# SlaveProtect.net
KiCad netlist of a schematic drawn in EAGLE
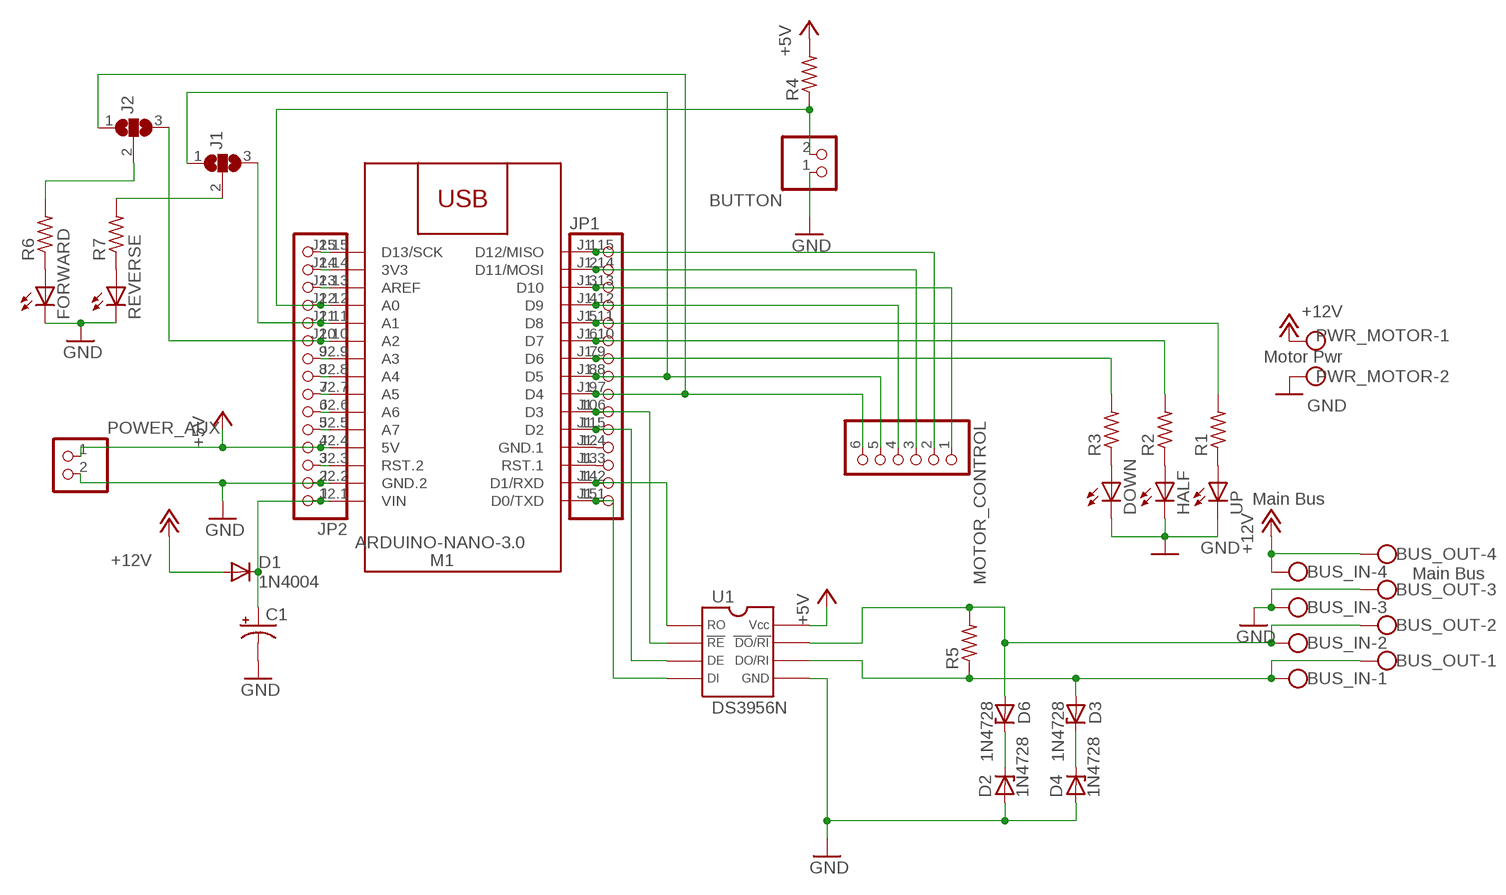
[diagram p0: schematic, sheet 1]

(export (version "E")
  (design (tool "Eeschema 10.0.6"))
  (components
    (comp (ref "BUS_IN")
      (value "Main Bus")
      (footprint "eagle-import:W237-4")
      (libsource (lib "eagle-import") (part "W237-4"))
    )
    (comp (ref "BUS_OUT")
      (value "Main Bus")
      (footprint "eagle-import:W237-4")
      (libsource (lib "eagle-import") (part "W237-4"))
    )
    (comp (ref "BUTTON")
      (value "PINHD-1X2")
      (footprint "eagle-import:1X02")
      (libsource (lib "eagle-import") (part "PINHD-1X2"))
    )
    (comp (ref "C1")
      (value "CPOL-USE3.5-10")
      (footprint "eagle-import:E3,5-10")
      (libsource (lib "eagle-import") (part "CPOL-USE3.5-10"))
    )
    (comp (ref "D1")
      (value "1N4004")
      (footprint "eagle-import:DO41-10")
      (libsource (lib "eagle-import") (part "1N4004"))
    )
    (comp (ref "D2")
      (value "1N4728")
      (footprint "eagle-import:DO41Z10")
      (libsource (lib "eagle-import") (part "1N4728"))
    )
    (comp (ref "D3")
      (value "1N4728")
      (footprint "eagle-import:DO41Z10")
      (libsource (lib "eagle-import") (part "1N4728"))
    )
    (comp (ref "D4")
      (value "1N4728")
      (footprint "eagle-import:DO41Z10")
      (libsource (lib "eagle-import") (part "1N4728"))
    )
    (comp (ref "D6")
      (value "1N4728")
      (footprint "eagle-import:DO41Z10")
      (libsource (lib "eagle-import") (part "1N4728"))
    )
    (comp (ref "DOWN")
      (value "LED5MM")
      (footprint "eagle-import:LED5MM")
      (libsource (lib "eagle-import") (part "LED5MM"))
    )
    (comp (ref "FORWARD")
      (value "LED5MM")
      (footprint "eagle-import:LED5MM")
      (libsource (lib "eagle-import") (part "LED5MM"))
    )
    (comp (ref "HALF")
      (value "LED5MM")
      (footprint "eagle-import:LED5MM")
      (libsource (lib "eagle-import") (part "LED5MM"))
    )
    (comp (ref "J1")
      (value "SJ2W")
      (footprint "eagle-import:SJ_2")
      (libsource (lib "eagle-import") (part "SJ2W"))
    )
    (comp (ref "J2")
      (value "SJ2W")
      (footprint "eagle-import:SJ_2")
      (libsource (lib "eagle-import") (part "SJ2W"))
    )
    (comp (ref "JP1")
      (value "PINHD-1X15-CB")
      (footprint "eagle-import:1X15-CB")
      (libsource (lib "eagle-import") (part "PINHD-1X15-CB"))
    )
    (comp (ref "JP2")
      (value "PINHD-1X15-CB")
      (footprint "eagle-import:1X15-CB")
      (libsource (lib "eagle-import") (part "PINHD-1X15-CB"))
    )
    (comp (ref "M1")
      (value "ARDUINO-NANO-3.0")
      (footprint "eagle-import:ARDUINO-NANO-3.0")
      (libsource (lib "eagle-import") (part "ARDUINO-NANO-3.0"))
    )
    (comp (ref "MOTOR_CONTROL")
      (value "PINHD-1X6")
      (footprint "eagle-import:1X06")
      (libsource (lib "eagle-import") (part "PINHD-1X6"))
    )
    (comp (ref "POWER_AUX")
      (value "PINHD-1X2")
      (footprint "eagle-import:1X02")
      (libsource (lib "eagle-import") (part "PINHD-1X2"))
    )
    (comp (ref "PWR_MOTOR")
      (value "Motor Pwr")
      (footprint "eagle-import:W237-102")
      (fields (field (name "MPN") "237-102"))
      (libsource (lib "eagle-import") (part "W237-102"))
    )
    (comp (ref "R1")
      (value "FLIPFLOP-RES")
      (footprint "eagle-import:0805-THM")
      (libsource (lib "eagle-import") (part "FLIPFLOP-RES"))
    )
    (comp (ref "R2")
      (value "FLIPFLOP-RES")
      (footprint "eagle-import:0805-THM")
      (libsource (lib "eagle-import") (part "FLIPFLOP-RES"))
    )
    (comp (ref "R3")
      (value "FLIPFLOP-RES")
      (footprint "eagle-import:0805-THM")
      (libsource (lib "eagle-import") (part "FLIPFLOP-RES"))
    )
    (comp (ref "R4")
      (value "FLIPFLOP-RES")
      (footprint "eagle-import:0805-THM")
      (libsource (lib "eagle-import") (part "FLIPFLOP-RES"))
    )
    (comp (ref "R5")
      (value "FLIPFLOP-RES")
      (footprint "eagle-import:0805-THM")
      (libsource (lib "eagle-import") (part "FLIPFLOP-RES"))
    )
    (comp (ref "R6")
      (value "FLIPFLOP-RES")
      (footprint "eagle-import:0805-THM")
      (libsource (lib "eagle-import") (part "FLIPFLOP-RES"))
    )
    (comp (ref "R7")
      (value "FLIPFLOP-RES")
      (footprint "eagle-import:0805-THM")
      (libsource (lib "eagle-import") (part "FLIPFLOP-RES"))
    )
    (comp (ref "REVERSE")
      (value "LED5MM")
      (footprint "eagle-import:LED5MM")
      (libsource (lib "eagle-import") (part "LED5MM"))
    )
    (comp (ref "U1")
      (value "DS3956N")
      (footprint "eagle-import:DIL08")
      (libsource (lib "eagle-import") (part "DS3956N"))
    )
    (comp (ref "UP")
      (value "LED5MM")
      (footprint "eagle-import:LED5MM")
      (libsource (lib "eagle-import") (part "LED5MM"))
    )
  )
  (nets
    (net (code "1") (name "+5V") (class "Default")
      (node (ref "JP2") (pin "4") (pinfunction "4_4") (pintype "passive"))
      (node (ref "M1") (pin "J2.4") (pinfunction "5V_J2.4") (pintype "power_in"))
      (node (ref "POWER_AUX") (pin "1") (pinfunction "1_1") (pintype "passive"))
      (node (ref "R4") (pin "2") (pinfunction "2_2") (pintype "passive"))
      (node (ref "U1") (pin "8") (pinfunction "VCC_8") (pintype "bidirectional"))
    )
    (net (code "2") (name "+12V") (class "Default")
      (node (ref "BUS_IN") (pin "4") (pinfunction "KL_4") (pintype "passive"))
      (node (ref "BUS_OUT") (pin "4") (pinfunction "KL_4") (pintype "passive"))
      (node (ref "D1") (pin "A") (pinfunction "A_A") (pintype "passive"))
      (node (ref "PWR_MOTOR") (pin "1") (pinfunction "KL_1") (pintype "passive"))
    )
    (net (code "3") (name "GND") (class "Default")
      (node (ref "BUS_IN") (pin "3") (pinfunction "KL_3") (pintype "passive"))
      (node (ref "BUS_OUT") (pin "3") (pinfunction "KL_3") (pintype "passive"))
      (node (ref "BUTTON") (pin "1") (pinfunction "1_1") (pintype "passive"))
      (node (ref "C1") (pin "-") (pinfunction "-_-") (pintype "passive"))
      (node (ref "D2") (pin "A") (pinfunction "A_A") (pintype "passive"))
      (node (ref "D4") (pin "A") (pinfunction "A_A") (pintype "passive"))
      (node (ref "DOWN") (pin "K") (pinfunction "C_K") (pintype "passive"))
      (node (ref "FORWARD") (pin "K") (pinfunction "C_K") (pintype "passive"))
      (node (ref "HALF") (pin "K") (pinfunction "C_K") (pintype "passive"))
      (node (ref "JP2") (pin "2") (pinfunction "2_2") (pintype "passive"))
      (node (ref "M1") (pin "J2.2") (pinfunction "GND.2_J2.2") (pintype "power_in"))
      (node (ref "POWER_AUX") (pin "2") (pinfunction "2_2") (pintype "passive"))
      (node (ref "PWR_MOTOR") (pin "2") (pinfunction "KL_2") (pintype "passive"))
      (node (ref "REVERSE") (pin "K") (pinfunction "C_K") (pintype "passive"))
      (node (ref "U1") (pin "5") (pinfunction "GND_5") (pintype "bidirectional"))
      (node (ref "UP") (pin "K") (pinfunction "C_K") (pintype "passive"))
    )
    (net (code "4") (name "Net-(BUS_INA-KL)") (class "Default")
      (node (ref "BUS_IN") (pin "1") (pinfunction "KL_1") (pintype "passive"))
      (node (ref "BUS_OUT") (pin "1") (pinfunction "KL_1") (pintype "passive"))
      (node (ref "D3") (pin "A") (pinfunction "A_A") (pintype "passive"))
      (node (ref "R5") (pin "1") (pinfunction "1_1") (pintype "passive"))
      (node (ref "U1") (pin "6") (pinfunction "DO/RI_6") (pintype "bidirectional"))
    )
    (net (code "5") (name "Net-(BUS_INB-KL)") (class "Default")
      (node (ref "BUS_IN") (pin "2") (pinfunction "KL_2") (pintype "passive"))
      (node (ref "BUS_OUT") (pin "2") (pinfunction "KL_2") (pintype "passive"))
      (node (ref "D6") (pin "A") (pinfunction "A_A") (pintype "passive"))
      (node (ref "R5") (pin "2") (pinfunction "2_2") (pintype "passive"))
      (node (ref "U1") (pin "7") (pinfunction "_DO/RI__7") (pintype "bidirectional"))
    )
    (net (code "6") (name "Net-(D2-PadC)") (class "Default")
      (node (ref "D2") (pin "C") (pinfunction "C_C") (pintype "passive"))
      (node (ref "D6") (pin "C") (pinfunction "C_C") (pintype "passive"))
    )
    (net (code "7") (name "Net-(D3-PadC)") (class "Default")
      (node (ref "D3") (pin "C") (pinfunction "C_C") (pintype "passive"))
      (node (ref "D4") (pin "C") (pinfunction "C_C") (pintype "passive"))
    )
    (net (code "8") (name "Net-(DOWN-PadA)") (class "Default")
      (node (ref "DOWN") (pin "A") (pinfunction "A_A") (pintype "passive"))
      (node (ref "R3") (pin "1") (pinfunction "1_1") (pintype "passive"))
    )
    (net (code "9") (name "Net-(FORWARD-PadA)") (class "Default")
      (node (ref "FORWARD") (pin "A") (pinfunction "A_A") (pintype "passive"))
      (node (ref "R6") (pin "1") (pinfunction "1_1") (pintype "passive"))
    )
    (net (code "10") (name "Net-(HALF-PadA)") (class "Default")
      (node (ref "HALF") (pin "A") (pinfunction "A_A") (pintype "passive"))
      (node (ref "R2") (pin "1") (pinfunction "1_1") (pintype "passive"))
    )
    (net (code "11") (name "Net-(J1-Pad2)") (class "Default")
      (node (ref "J1") (pin "2") (pinfunction "2_2") (pintype "passive"))
      (node (ref "R7") (pin "2") (pinfunction "2_2") (pintype "passive"))
    )
    (net (code "12") (name "Net-(J2-Pad2)") (class "Default")
      (node (ref "J2") (pin "2") (pinfunction "2_2") (pintype "passive"))
      (node (ref "R6") (pin "2") (pinfunction "2_2") (pintype "passive"))
    )
    (net (code "13") (name "Net-(M1-3V3)") (class "Default")
      (node (ref "JP2") (pin "14") (pinfunction "14_14") (pintype "passive"))
      (node (ref "M1") (pin "J2.14") (pinfunction "3V3_J2.14") (pintype "power_in"))
    )
    (net (code "14") (name "Net-(M1-A0)") (class "Default")
      (node (ref "BUTTON") (pin "2") (pinfunction "2_2") (pintype "passive"))
      (node (ref "JP2") (pin "12") (pinfunction "12_12") (pintype "passive"))
      (node (ref "M1") (pin "J2.12") (pinfunction "A0_J2.12") (pintype "bidirectional"))
      (node (ref "R4") (pin "1") (pinfunction "1_1") (pintype "passive"))
    )
    (net (code "15") (name "Net-(M1-A1)") (class "Default")
      (node (ref "J1") (pin "3") (pinfunction "3_3") (pintype "passive"))
      (node (ref "JP2") (pin "11") (pinfunction "11_11") (pintype "passive"))
      (node (ref "M1") (pin "J2.11") (pinfunction "A1_J2.11") (pintype "bidirectional"))
    )
    (net (code "16") (name "Net-(M1-A2)") (class "Default")
      (node (ref "J2") (pin "3") (pinfunction "3_3") (pintype "passive"))
      (node (ref "JP2") (pin "10") (pinfunction "10_10") (pintype "passive"))
      (node (ref "M1") (pin "J2.10") (pinfunction "A2_J2.10") (pintype "bidirectional"))
    )
    (net (code "17") (name "Net-(M1-A3)") (class "Default")
      (node (ref "JP2") (pin "9") (pinfunction "9_9") (pintype "passive"))
      (node (ref "M1") (pin "J2.9") (pinfunction "A3_J2.9") (pintype "bidirectional"))
    )
    (net (code "18") (name "Net-(M1-A4)") (class "Default")
      (node (ref "JP2") (pin "8") (pinfunction "8_8") (pintype "passive"))
      (node (ref "M1") (pin "J2.8") (pinfunction "A4_J2.8") (pintype "bidirectional"))
    )
    (net (code "19") (name "Net-(M1-A5)") (class "Default")
      (node (ref "JP2") (pin "7") (pinfunction "7_7") (pintype "passive"))
      (node (ref "M1") (pin "J2.7") (pinfunction "A5_J2.7") (pintype "bidirectional"))
    )
    (net (code "20") (name "Net-(M1-A6)") (class "Default")
      (node (ref "JP2") (pin "6") (pinfunction "6_6") (pintype "passive"))
      (node (ref "M1") (pin "J2.6") (pinfunction "A6_J2.6") (pintype "bidirectional"))
    )
    (net (code "21") (name "Net-(M1-A7)") (class "Default")
      (node (ref "JP2") (pin "5") (pinfunction "5_5") (pintype "passive"))
      (node (ref "M1") (pin "J2.5") (pinfunction "A7_J2.5") (pintype "bidirectional"))
    )
    (net (code "22") (name "Net-(M1-AREF)") (class "Default")
      (node (ref "JP2") (pin "13") (pinfunction "13_13") (pintype "passive"))
      (node (ref "M1") (pin "J2.13") (pinfunction "AREF_J2.13") (pintype "bidirectional"))
    )
    (net (code "23") (name "Net-(M1-D0{slash}TXD)") (class "Default")
      (node (ref "JP1") (pin "15") (pinfunction "15_15") (pintype "passive"))
      (node (ref "M1") (pin "J1.1") (pinfunction "D0/TXD_J1.1") (pintype "bidirectional"))
      (node (ref "U1") (pin "4") (pinfunction "DI_4") (pintype "bidirectional"))
    )
    (net (code "24") (name "Net-(M1-D1{slash}RXD)") (class "Default")
      (node (ref "JP1") (pin "14") (pinfunction "14_14") (pintype "passive"))
      (node (ref "M1") (pin "J1.2") (pinfunction "D1/RXD_J1.2") (pintype "bidirectional"))
      (node (ref "U1") (pin "1") (pinfunction "RO_1") (pintype "bidirectional"))
    )
    (net (code "25") (name "Net-(M1-D2)") (class "Default")
      (node (ref "JP1") (pin "11") (pinfunction "11_11") (pintype "passive"))
      (node (ref "M1") (pin "J1.5") (pinfunction "D2_J1.5") (pintype "bidirectional"))
      (node (ref "U1") (pin "3") (pinfunction "DE_3") (pintype "bidirectional"))
    )
    (net (code "26") (name "Net-(M1-D3)") (class "Default")
      (node (ref "JP1") (pin "10") (pinfunction "10_10") (pintype "passive"))
      (node (ref "M1") (pin "J1.6") (pinfunction "D3_J1.6") (pintype "bidirectional"))
      (node (ref "U1") (pin "2") (pinfunction "_RE__2") (pintype "bidirectional"))
    )
    (net (code "27") (name "Net-(M1-D4)") (class "Default")
      (node (ref "J2") (pin "1") (pinfunction "1_1") (pintype "passive"))
      (node (ref "JP1") (pin "9") (pinfunction "9_9") (pintype "passive"))
      (node (ref "M1") (pin "J1.7") (pinfunction "D4_J1.7") (pintype "bidirectional"))
      (node (ref "MOTOR_CONTROL") (pin "6") (pinfunction "6_6") (pintype "passive"))
    )
    (net (code "28") (name "Net-(M1-D5)") (class "Default")
      (node (ref "J1") (pin "1") (pinfunction "1_1") (pintype "passive"))
      (node (ref "JP1") (pin "8") (pinfunction "8_8") (pintype "passive"))
      (node (ref "M1") (pin "J1.8") (pinfunction "D5_J1.8") (pintype "bidirectional"))
      (node (ref "MOTOR_CONTROL") (pin "5") (pinfunction "5_5") (pintype "passive"))
    )
    (net (code "29") (name "Net-(M1-D6)") (class "Default")
      (node (ref "JP1") (pin "7") (pinfunction "7_7") (pintype "passive"))
      (node (ref "M1") (pin "J1.9") (pinfunction "D6_J1.9") (pintype "bidirectional"))
      (node (ref "R3") (pin "2") (pinfunction "2_2") (pintype "passive"))
    )
    (net (code "30") (name "Net-(M1-D7)") (class "Default")
      (node (ref "JP1") (pin "6") (pinfunction "6_6") (pintype "passive"))
      (node (ref "M1") (pin "J1.10") (pinfunction "D7_J1.10") (pintype "bidirectional"))
      (node (ref "R2") (pin "2") (pinfunction "2_2") (pintype "passive"))
    )
    (net (code "31") (name "Net-(M1-D8)") (class "Default")
      (node (ref "JP1") (pin "5") (pinfunction "5_5") (pintype "passive"))
      (node (ref "M1") (pin "J1.11") (pinfunction "D8_J1.11") (pintype "bidirectional"))
      (node (ref "R1") (pin "2") (pinfunction "2_2") (pintype "passive"))
    )
    (net (code "32") (name "Net-(M1-D9)") (class "Default")
      (node (ref "JP1") (pin "4") (pinfunction "4_4") (pintype "passive"))
      (node (ref "M1") (pin "J1.12") (pinfunction "D9_J1.12") (pintype "bidirectional"))
      (node (ref "MOTOR_CONTROL") (pin "4") (pinfunction "4_4") (pintype "passive"))
    )
    (net (code "33") (name "Net-(M1-D10)") (class "Default")
      (node (ref "JP1") (pin "3") (pinfunction "3_3") (pintype "passive"))
      (node (ref "M1") (pin "J1.13") (pinfunction "D10_J1.13") (pintype "bidirectional"))
      (node (ref "MOTOR_CONTROL") (pin "1") (pinfunction "1_1") (pintype "passive"))
    )
    (net (code "34") (name "Net-(M1-D11{slash}MOSI)") (class "Default")
      (node (ref "JP1") (pin "2") (pinfunction "2_2") (pintype "passive"))
      (node (ref "M1") (pin "J1.14") (pinfunction "D11/MOSI_J1.14") (pintype "bidirectional"))
      (node (ref "MOTOR_CONTROL") (pin "3") (pinfunction "3_3") (pintype "passive"))
    )
    (net (code "35") (name "Net-(M1-D12{slash}MISO)") (class "Default")
      (node (ref "JP1") (pin "1") (pinfunction "1_1") (pintype "passive"))
      (node (ref "M1") (pin "J1.15") (pinfunction "D12/MISO_J1.15") (pintype "bidirectional"))
      (node (ref "MOTOR_CONTROL") (pin "2") (pinfunction "2_2") (pintype "passive"))
    )
    (net (code "36") (name "Net-(M1-D13{slash}SCK)") (class "Default")
      (node (ref "JP2") (pin "15") (pinfunction "15_15") (pintype "passive"))
      (node (ref "M1") (pin "J2.15") (pinfunction "D13/SCK_J2.15") (pintype "bidirectional"))
    )
    (net (code "37") (name "Net-(M1-GND.1)") (class "Default")
      (node (ref "JP1") (pin "12") (pinfunction "12_12") (pintype "passive"))
      (node (ref "M1") (pin "J1.4") (pinfunction "GND.1_J1.4") (pintype "power_in"))
    )
    (net (code "38") (name "Net-(M1-RST.1)") (class "Default")
      (node (ref "JP1") (pin "13") (pinfunction "13_13") (pintype "passive"))
      (node (ref "M1") (pin "J1.3") (pinfunction "RST.1_J1.3") (pintype "bidirectional"))
    )
    (net (code "39") (name "Net-(M1-RST.2)") (class "Default")
      (node (ref "JP2") (pin "3") (pinfunction "3_3") (pintype "passive"))
      (node (ref "M1") (pin "J2.3") (pinfunction "RST.2_J2.3") (pintype "bidirectional"))
    )
    (net (code "40") (name "Net-(M1-VIN)") (class "Default")
      (node (ref "C1") (pin "+") (pinfunction "+_+") (pintype "passive"))
      (node (ref "D1") (pin "C") (pinfunction "C_C") (pintype "passive"))
      (node (ref "JP2") (pin "1") (pinfunction "1_1") (pintype "passive"))
      (node (ref "M1") (pin "J2.1") (pinfunction "VIN_J2.1") (pintype "power_in"))
    )
    (net (code "41") (name "Net-(R1-Pad1)") (class "Default")
      (node (ref "R1") (pin "1") (pinfunction "1_1") (pintype "passive"))
      (node (ref "UP") (pin "A") (pinfunction "A_A") (pintype "passive"))
    )
    (net (code "42") (name "Net-(R7-Pad1)") (class "Default")
      (node (ref "R7") (pin "1") (pinfunction "1_1") (pintype "passive"))
      (node (ref "REVERSE") (pin "A") (pinfunction "A_A") (pintype "passive"))
    )
  )
)
